# minireg-adp7102.net
KiCad netlist of a schematic drawn in Altium Designer
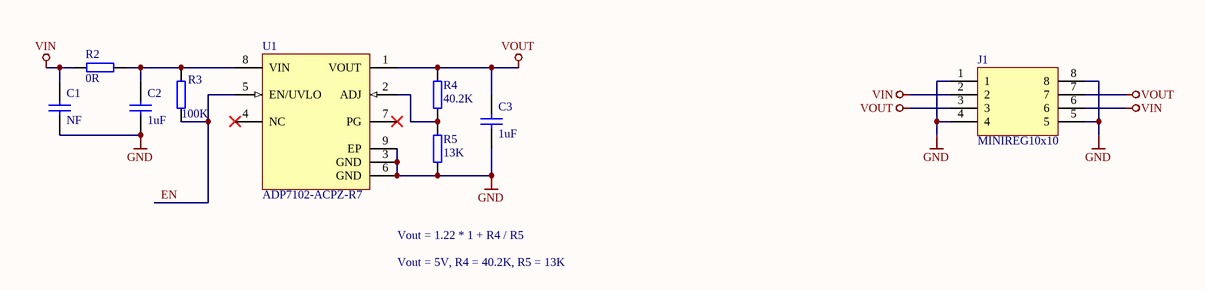
[diagram p0: minireg-adp7102.SchDoc]

(export (version "E")
  (design (tool "Eeschema 10.0.6"))
  (components
    (comp (ref "C1")
      (value "NF")
      (footprint "CAP0603")
      (description "CAP SM 0603 N/F")
      (fields (field (name "PART NUMBER") "CAP-SM-0603-NF") (field (name "MANUFACTURER") "GENERIC"))
      (libsource (lib "electronpowered") (part "CAP"))
    )
    (comp (ref "C2")
      (value "1uF")
      (footprint "CAP0603")
      (description "CAP SM 0603 X7R 1uF")
      (fields (field (name "PART NUMBER") "CAP-SM-0603-X7R-1uF") (field (name "MANUFACTURER") "GENERIC"))
      (libsource (lib "electronpowered") (part "CAP"))
    )
    (comp (ref "C3")
      (value "1uF")
      (footprint "CAP0603")
      (description "CAP SM 0603 X7R 1uF")
      (fields (field (name "PART NUMBER") "CAP-SM-0603-X7R-1uF") (field (name "MANUFACTURER") "GENERIC"))
      (libsource (lib "electronpowered") (part "CAP"))
    )
    (comp (ref "J1")
      (value "MINIREG10x10")
      (footprint "MINIREG8_10x10R")
      (libsource (lib "minireg") (part "MINIREG10x10"))
    )
    (comp (ref "R2")
      (value "0R")
      (footprint "RES0603")
      (description "RES SM 0603 0R")
      (fields (field (name "PART NUMBER") "RES-SM-0603-0R") (field (name "MANUFACTURER") "GENERIC"))
      (libsource (lib "electronpowered") (part "RES"))
    )
    (comp (ref "R3")
      (value "100K")
      (footprint "RES0603")
      (description "RES SM 0603 100K")
      (fields (field (name "PART NUMBER") "RES-SM-0603-100K") (field (name "MANUFACTURER") "GENERIC"))
      (libsource (lib "electronpowered") (part "RES"))
    )
    (comp (ref "R4")
      (value "40.2K")
      (footprint "RES0603")
      (description "RES SM 0603 40.2K")
      (fields (field (name "PART NUMBER") "RES-SM-0603-40.2K") (field (name "MANUFACTURER") "GENERIC"))
      (libsource (lib "electronpowered") (part "RES"))
    )
    (comp (ref "R5")
      (value "13K")
      (footprint "RES0603")
      (description "RES SM 0603 10K")
      (fields (field (name "PART NUMBER") "RES-SM-0603-13K") (field (name "MANUFACTURER") "GENERIC"))
      (libsource (lib "electronpowered") (part "RES"))
    )
    (comp (ref "U1")
      (value "ADP7102-ACPZ-R7")
      (footprint "ADP7102ACPZ-R7")
      (fields (field (name "MANUFACTURER") "Analog Devices") (field (name "PARTNUMBER") "ADP7102ACPZ-R7"))
      (libsource (lib "minireg") (part "ADP7102-ACPZ"))
    )
  )
  (nets
    (net (code "1") (name "/EN") (class "Default")
      (node (ref "R3") (pin "1") (pinfunction "1_1") (pintype "passive"))
      (node (ref "U1") (pin "5") (pinfunction "EN/UVLO_5") (pintype "input"))
    )
    (net (code "2") (name "GND") (class "Default")
      (node (ref "C1") (pin "1") (pinfunction "1_1") (pintype "passive"))
      (node (ref "C2") (pin "1") (pinfunction "1_1") (pintype "passive"))
      (node (ref "C3") (pin "1") (pinfunction "1_1") (pintype "passive"))
      (node (ref "J1") (pin "1") (pinfunction "1_1") (pintype "power_in"))
      (node (ref "J1") (pin "4") (pinfunction "4_4") (pintype "power_in"))
      (node (ref "J1") (pin "5") (pinfunction "5_5") (pintype "power_in"))
      (node (ref "J1") (pin "8") (pinfunction "8_8") (pintype "power_in"))
      (node (ref "R5") (pin "1") (pinfunction "1_1") (pintype "passive"))
      (node (ref "U1") (pin "3") (pinfunction "GND_3") (pintype "power_in"))
      (node (ref "U1") (pin "6") (pinfunction "GND_6") (pintype "power_in"))
      (node (ref "U1") (pin "9") (pinfunction "EP_9") (pintype "power_in"))
    )
    (net (code "3") (name "Net-(U1-ADJ)") (class "Default")
      (node (ref "R4") (pin "1") (pinfunction "1_1") (pintype "passive"))
      (node (ref "R5") (pin "2") (pinfunction "2_2") (pintype "passive"))
      (node (ref "U1") (pin "2") (pinfunction "ADJ_2") (pintype "input"))
    )
    (net (code "4") (name "Net-(U1-VIN)") (class "Default")
      (node (ref "C2") (pin "2") (pinfunction "2_2") (pintype "passive"))
      (node (ref "R2") (pin "2") (pinfunction "2_2") (pintype "passive"))
      (node (ref "R3") (pin "2") (pinfunction "2_2") (pintype "passive"))
      (node (ref "U1") (pin "8") (pinfunction "VIN_8") (pintype "power_in"))
    )
    (net (code "5") (name "VIN") (class "Default")
      (node (ref "C1") (pin "2") (pinfunction "2_2") (pintype "passive"))
      (node (ref "J1") (pin "2") (pinfunction "2_2") (pintype "power_in"))
      (node (ref "J1") (pin "6") (pinfunction "6_6") (pintype "power_in"))
      (node (ref "R2") (pin "1") (pinfunction "1_1") (pintype "passive"))
    )
    (net (code "6") (name "VOUT") (class "Default")
      (node (ref "C3") (pin "2") (pinfunction "2_2") (pintype "passive"))
      (node (ref "J1") (pin "3") (pinfunction "3_3") (pintype "power_in"))
      (node (ref "J1") (pin "7") (pinfunction "7_7") (pintype "power_in"))
      (node (ref "R4") (pin "2") (pinfunction "2_2") (pintype "passive"))
      (node (ref "U1") (pin "1") (pinfunction "VOUT_1") (pintype "power_in"))
    )
    (net (code "7") (name "unconnected-(U1-NC-Pad4)") (class "Default")
      (node (ref "U1") (pin "4") (pinfunction "NC_4") (pintype "passive+no_connect"))
    )
    (net (code "8") (name "unconnected-(U1-PG-Pad7)") (class "Default")
      (node (ref "U1") (pin "7") (pinfunction "PG_7") (pintype "open_collector+no_connect"))
    )
  )
)
